# Control_Interface.net
KiCad netlist of a schematic drawn in Altium Designer
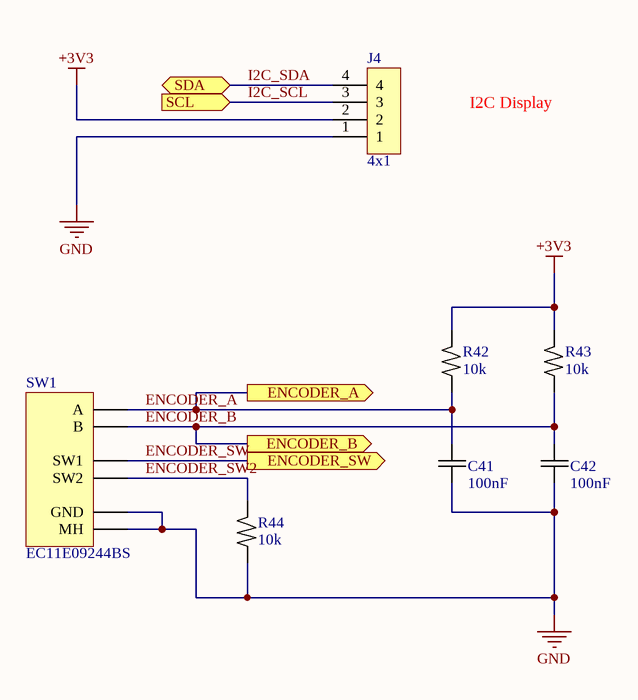
[diagram p0: Control Interface.SchDoc]

(export (version "E")
  (design (tool "Eeschema 10.0.6"))
  (components
    (comp (ref "C41")
      (value "100nF")
      (footprint "C0603")
      (description "CAP CER 100nF 50V X7R 0603")
      (fields (field (name "MF") "HRE") (field (name "MP") "CGA0603X7R104K500JT"))
      (libsource (lib "Components") (part "Cap_cer"))
    )
    (comp (ref "C42")
      (value "100nF")
      (footprint "C0603")
      (description "CAP CER 100nF 50V X7R 0603")
      (fields (field (name "MF") "HRE") (field (name "MP") "CGA0603X7R104K500JT"))
      (libsource (lib "Components") (part "Cap_cer"))
    )
    (comp (ref "J4")
      (value "4x1")
      (footprint "Female Header 4x1 2.54mm")
      (description "CONN SOCKET 4POS 2.54mm SINGLE ROW TH")
      (fields (field (name "MF") "BOOMELE(Boom Precision Elec)") (field (name "MP") "2.54-1*4P"))
      (libsource (lib "Connectors") (part "Pin Header Female 4x1 2.54mm"))
    )
    (comp (ref "R42")
      (value "10k")
      (footprint "R0603")
      (description "RES 10kΩ ±1% 100mW 0603")
      (fields (field (name "MF") "FOJAN") (field (name "MP") "FRC0603F1002TS"))
      (libsource (lib "Components") (part "Res"))
    )
    (comp (ref "R43")
      (value "10k")
      (footprint "R0603")
      (description "RES 10kΩ ±1% 100mW 0603")
      (fields (field (name "MF") "FOJAN") (field (name "MP") "FRC0603F1002TS"))
      (libsource (lib "Components") (part "Res"))
    )
    (comp (ref "R44")
      (value "10k")
      (footprint "R0603")
      (description "RES 10kΩ ±1% 100mW 0603")
      (fields (field (name "MF") "FOJAN") (field (name "MP") "FRC0603F1002TS"))
      (libsource (lib "Components") (part "Res"))
    )
    (comp (ref "SW1")
      (value "EC11E09244BS")
      (footprint "EC11E09244BS Encoder")
      (description "Through Hole Encoders RoHS")
      (fields (field (name "MF") "ALPSALPINE"))
      (libsource (lib "Components") (part "EC11E09244BS Encoder"))
    )
  )
  (nets
    (net (code "1") (name "+3V3") (class "Default")
      (node (ref "J4") (pin "2") (pinfunction "2_2") (pintype "passive"))
      (node (ref "R42") (pin "2") (pinfunction "2_2") (pintype "passive"))
      (node (ref "R43") (pin "2") (pinfunction "2_2") (pintype "passive"))
    )
    (net (code "2") (name "/ENCODER_A") (class "Default")
      (node (ref "C41") (pin "2") (pinfunction "2_2") (pintype "passive"))
      (node (ref "R42") (pin "1") (pinfunction "1_1") (pintype "passive"))
      (node (ref "SW1") (pin "A") (pinfunction "A_A") (pintype "passive"))
    )
    (net (code "3") (name "/ENCODER_B") (class "Default")
      (node (ref "C42") (pin "2") (pinfunction "2_2") (pintype "passive"))
      (node (ref "R43") (pin "1") (pinfunction "1_1") (pintype "passive"))
      (node (ref "SW1") (pin "B") (pinfunction "B_B") (pintype "passive"))
    )
    (net (code "4") (name "/ENCODER_SW") (class "Default")
      (node (ref "SW1") (pin "D") (pinfunction "SW1_D") (pintype "passive"))
    )
    (net (code "5") (name "/ENCODER_SW2") (class "Default")
      (node (ref "R44") (pin "2") (pinfunction "2_2") (pintype "passive"))
      (node (ref "SW1") (pin "E") (pinfunction "SW2_E") (pintype "passive"))
    )
    (net (code "6") (name "/I2C_SCL") (class "Default")
      (node (ref "J4") (pin "3") (pinfunction "3_3") (pintype "passive"))
    )
    (net (code "7") (name "/I2C_SDA") (class "Default")
      (node (ref "J4") (pin "4") (pinfunction "4_4") (pintype "passive"))
    )
    (net (code "8") (name "GND") (class "Default")
      (node (ref "C41") (pin "1") (pinfunction "1_1") (pintype "passive"))
      (node (ref "C42") (pin "1") (pinfunction "1_1") (pintype "passive"))
      (node (ref "J4") (pin "1") (pinfunction "1_1") (pintype "passive"))
      (node (ref "R44") (pin "1") (pinfunction "1_1") (pintype "passive"))
      (node (ref "SW1") (pin "C") (pinfunction "GND_C") (pintype "passive"))
      (node (ref "SW1") (pin "MH") (pinfunction "MH_MH") (pintype "passive"))
    )
  )
)
